# APDS-9008_Breakout.net
KiCad netlist of a schematic drawn in EAGLE
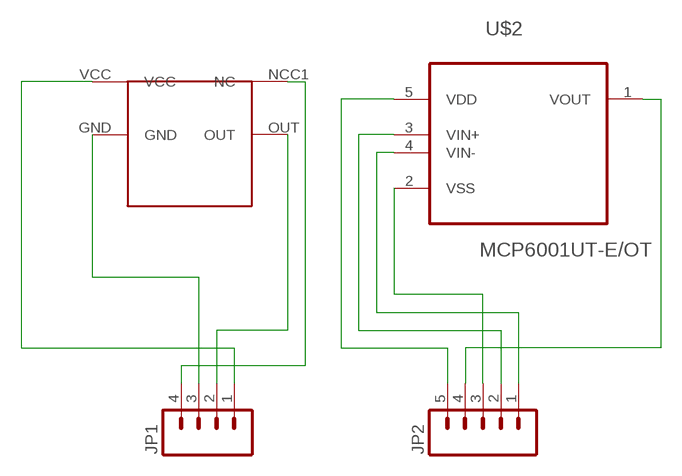
[diagram p0: schematic, sheet 1]

(export (version "E")
  (design (tool "Eeschema 10.0.6"))
  (components
    (comp (ref "JP1")
      (value "M04LOCK")
      (footprint "eagle-import:1X04_LOCK")
      (libsource (lib "eagle-import") (part "M04LOCK"))
    )
    (comp (ref "JP2")
      (value "M05LOCK")
      (footprint "eagle-import:1X05_LOCK")
      (libsource (lib "eagle-import") (part "M05LOCK"))
    )
    (comp (ref "U$1")
      (value "APDS9008")
      (footprint "eagle-import:APDS9008")
      (libsource (lib "eagle-import") (part "APDS9008"))
    )
    (comp (ref "U$2")
      (value "MCP6001UT-E/OT")
      (footprint "eagle-import:SOT95P270X145-5N")
      (libsource (lib "eagle-import") (part "MCP6001UT-E/OT"))
    )
  )
  (nets
    (net (code "1") (name "Net-(JP1-Pad1)") (class "Default")
      (node (ref "JP1") (pin "1") (pinfunction "1_1") (pintype "passive"))
      (node (ref "U$1") (pin "VCC") (pinfunction "VCC_VCC") (pintype "bidirectional"))
    )
    (net (code "2") (name "Net-(JP1-Pad2)") (class "Default")
      (node (ref "JP1") (pin "2") (pinfunction "2_2") (pintype "passive"))
      (node (ref "U$1") (pin "OUT") (pinfunction "OUT_OUT") (pintype "bidirectional"))
    )
    (net (code "3") (name "Net-(JP1-Pad3)") (class "Default")
      (node (ref "JP1") (pin "3") (pinfunction "3_3") (pintype "passive"))
      (node (ref "U$1") (pin "GND") (pinfunction "GND_GND") (pintype "bidirectional"))
    )
    (net (code "4") (name "Net-(U$1-NC)") (class "Default")
      (node (ref "JP1") (pin "4") (pinfunction "4_4") (pintype "passive"))
      (node (ref "U$1") (pin "NCC1") (pinfunction "NC_NCC1") (pintype "bidirectional"))
    )
    (net (code "5") (name "Net-(U$2-VDD)") (class "Default")
      (node (ref "JP2") (pin "5") (pinfunction "5_5") (pintype "passive"))
      (node (ref "U$2") (pin "5") (pinfunction "VDD_5") (pintype "power_in"))
    )
    (net (code "6") (name "Net-(U$2-VIN+)") (class "Default")
      (node (ref "JP2") (pin "2") (pinfunction "2_2") (pintype "passive"))
      (node (ref "U$2") (pin "3") (pinfunction "VIN+_3") (pintype "input"))
    )
    (net (code "7") (name "Net-(U$2-VIN-)") (class "Default")
      (node (ref "JP2") (pin "1") (pinfunction "1_1") (pintype "passive"))
      (node (ref "U$2") (pin "4") (pinfunction "VIN-_4") (pintype "input"))
    )
    (net (code "8") (name "Net-(U$2-VOUT)") (class "Default")
      (node (ref "JP2") (pin "4") (pinfunction "4_4") (pintype "passive"))
      (node (ref "U$2") (pin "1") (pinfunction "VOUT_1") (pintype "output"))
    )
    (net (code "9") (name "Net-(U$2-VSS)") (class "Default")
      (node (ref "JP2") (pin "3") (pinfunction "3_3") (pintype "passive"))
      (node (ref "U$2") (pin "2") (pinfunction "VSS_2") (pintype "passive"))
    )
  )
)
